# PCBArduino.net
KiCad netlist of a schematic drawn in EAGLE
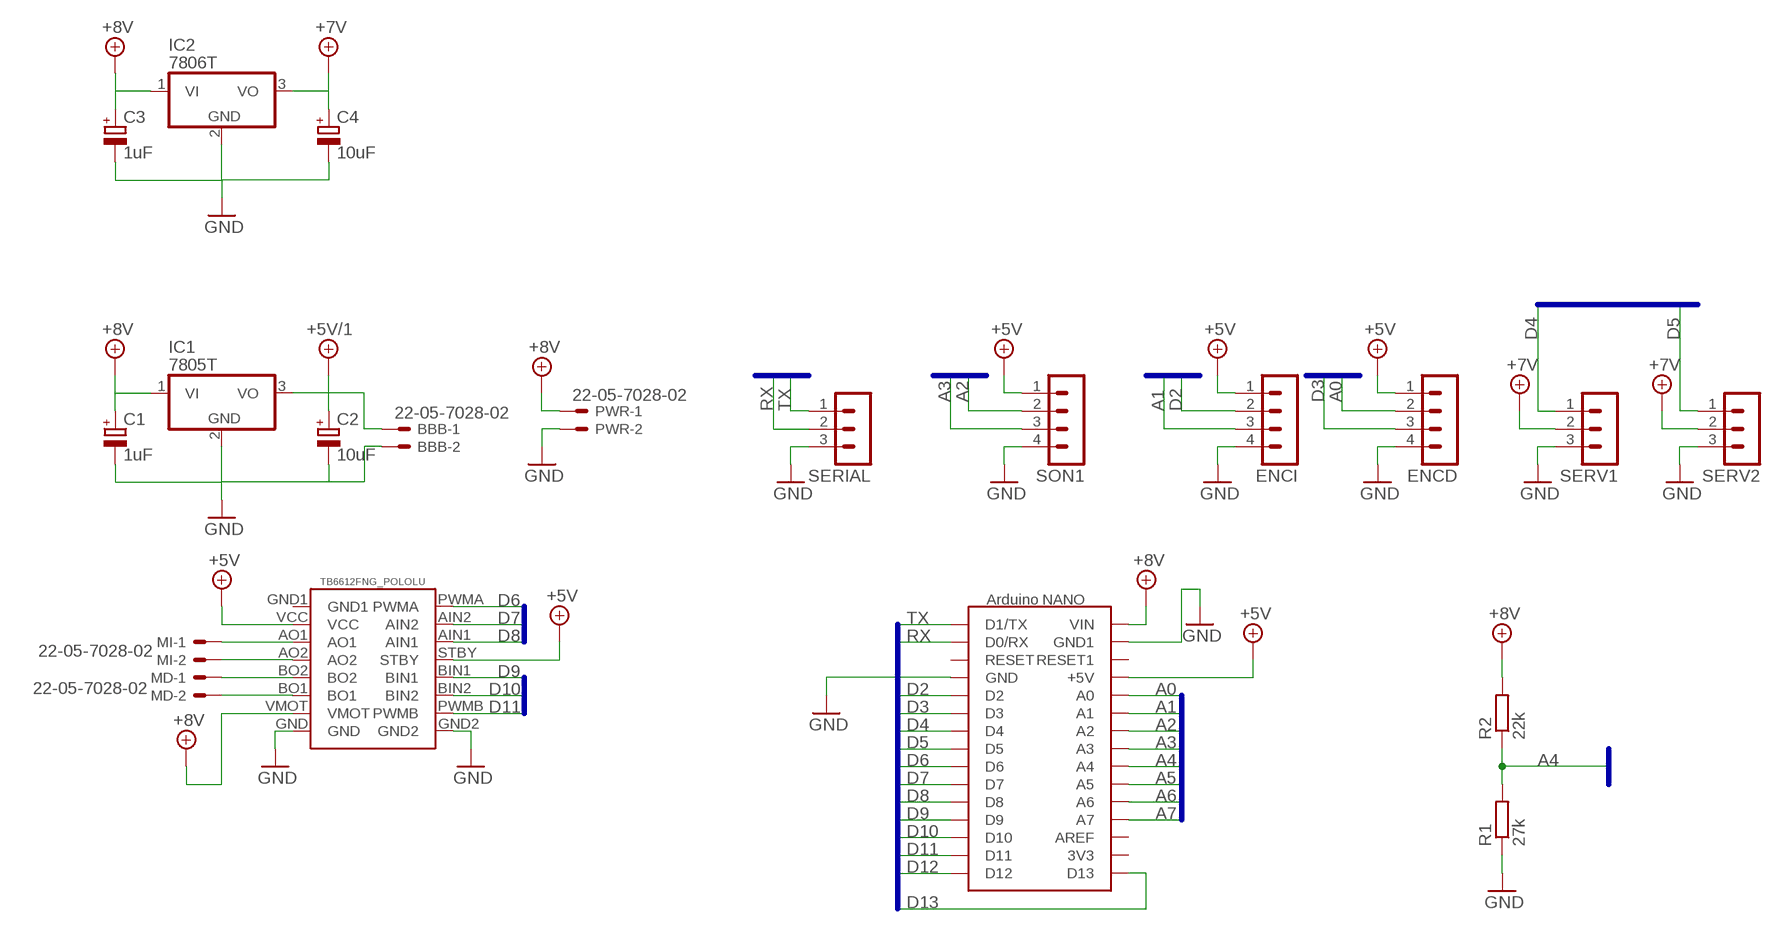
[diagram p0: schematic, sheet 1]

(export (version "E")
  (design (tool "Eeschema 10.0.6"))
  (components
    (comp (ref "BBB")
      (value "22-05-7028-02")
      (footprint "eagle-import:7395-02")
      (fields (field (name "OC_FARNELL") "9731601") (field (name "OC_NEWARK") "unknown"))
      (libsource (lib "eagle-import") (part "22-?-0205-7028"))
    )
    (comp (ref "C1")
      (value "1uF")
      (footprint "eagle-import:E2,5-7")
      (libsource (lib "eagle-import") (part "CPOL-EUE2.5-7"))
    )
    (comp (ref "C2")
      (value "10uF")
      (footprint "eagle-import:E2,5-7")
      (libsource (lib "eagle-import") (part "CPOL-EUE2.5-7"))
    )
    (comp (ref "C3")
      (value "1uF")
      (footprint "eagle-import:E2,5-7")
      (libsource (lib "eagle-import") (part "CPOL-EUE2.5-7"))
    )
    (comp (ref "C4")
      (value "10uF")
      (footprint "eagle-import:E2,5-7")
      (libsource (lib "eagle-import") (part "CPOL-EUE2.5-7"))
    )
    (comp (ref "ENCD")
      (value "MA04-1")
      (footprint "eagle-import:MA04-1")
      (libsource (lib "eagle-import") (part "MA04-1"))
    )
    (comp (ref "ENCI")
      (value "MA04-1")
      (footprint "eagle-import:MA04-1")
      (libsource (lib "eagle-import") (part "MA04-1"))
    )
    (comp (ref "IC1")
      (value "7805T")
      (footprint "eagle-import:TO220H")
      (libsource (lib "eagle-import") (part "78T05"))
    )
    (comp (ref "IC2")
      (value "7806T")
      (footprint "eagle-import:TO220H")
      (libsource (lib "eagle-import") (part "78T06"))
    )
    (comp (ref "MD")
      (value "22-05-7028-02")
      (footprint "eagle-import:7395-02")
      (libsource (lib "eagle-import") (part "22-?-0205-7028"))
    )
    (comp (ref "MI")
      (value "22-05-7028-02")
      (footprint "eagle-import:7395-02")
      (libsource (lib "eagle-import") (part "22-?-0205-7028"))
    )
    (comp (ref "PWR")
      (value "22-05-7028-02")
      (footprint "eagle-import:7395-02")
      (libsource (lib "eagle-import") (part "22-?-0205-7028"))
    )
    (comp (ref "R1")
      (value "27k")
      (footprint "eagle-import:0204_5")
      (libsource (lib "eagle-import") (part "R-EU_0204/5"))
    )
    (comp (ref "R2")
      (value "22k")
      (footprint "eagle-import:0204_5")
      (libsource (lib "eagle-import") (part "R-EU_0204/5"))
    )
    (comp (ref "SERIAL")
      (value "MA03-1")
      (footprint "eagle-import:MA03-1")
      (libsource (lib "eagle-import") (part "MA03-1"))
    )
    (comp (ref "SERV1")
      (value "MA03-1")
      (footprint "eagle-import:MA03-1")
      (libsource (lib "eagle-import") (part "MA03-1"))
    )
    (comp (ref "SERV2")
      (value "MA03-1")
      (footprint "eagle-import:MA03-1")
      (libsource (lib "eagle-import") (part "MA03-1"))
    )
    (comp (ref "SON1")
      (value "MA04-1")
      (footprint "eagle-import:MA04-1")
      (fields (field (name "OC_FARNELL") "unknown") (field (name "OC_NEWARK") "unknown"))
      (libsource (lib "eagle-import") (part "MA04-1"))
    )
    (comp (ref "U$1")
      (value "ARDUINONANO")
      (footprint "eagle-import:PDIP-32")
      (libsource (lib "eagle-import") (part "ARDUINONANO"))
    )
    (comp (ref "U$2")
      (value "TB6612FNG_POLOLU")
      (footprint "eagle-import:TB6612FNG_POLOLU")
      (libsource (lib "eagle-import") (part "TB6612FNG_POLOLU"))
    )
  )
  (nets
    (net (code "1") (name "+5V") (class "Default")
      (node (ref "ENCD") (pin "1") (pinfunction "1_1") (pintype "passive"))
      (node (ref "ENCI") (pin "1") (pinfunction "1_1") (pintype "passive"))
      (node (ref "SON1") (pin "1") (pinfunction "1_1") (pintype "passive"))
      (node (ref "U$1") (pin "+5V") (pinfunction "+5V_+5V") (pintype "bidirectional"))
      (node (ref "U$2") (pin "STBY") (pinfunction "STBY_STBY") (pintype "bidirectional"))
      (node (ref "U$2") (pin "VCC") (pinfunction "VCC_VCC") (pintype "bidirectional"))
    )
    (net (code "2") (name "+5V{slash}1") (class "Default")
      (node (ref "BBB") (pin "1") (pinfunction "S_1") (pintype "passive"))
      (node (ref "C2") (pin "+") (pinfunction "+_+") (pintype "passive"))
      (node (ref "IC1") (pin "3") (pinfunction "VO_3") (pintype "passive"))
    )
    (net (code "3") (name "+7V") (class "Default")
      (node (ref "C4") (pin "+") (pinfunction "+_+") (pintype "passive"))
      (node (ref "IC2") (pin "3") (pinfunction "VO_3") (pintype "passive"))
      (node (ref "SERV1") (pin "2") (pinfunction "2_2") (pintype "passive"))
      (node (ref "SERV2") (pin "2") (pinfunction "2_2") (pintype "passive"))
    )
    (net (code "4") (name "+8V") (class "Default")
      (node (ref "C1") (pin "+") (pinfunction "+_+") (pintype "passive"))
      (node (ref "C3") (pin "+") (pinfunction "+_+") (pintype "passive"))
      (node (ref "IC1") (pin "1") (pinfunction "VI_1") (pintype "input"))
      (node (ref "IC2") (pin "1") (pinfunction "VI_1") (pintype "input"))
      (node (ref "PWR") (pin "1") (pinfunction "S_1") (pintype "passive"))
      (node (ref "R2") (pin "2") (pinfunction "2_2") (pintype "passive"))
      (node (ref "U$1") (pin "VIN") (pinfunction "VIN_VIN") (pintype "bidirectional"))
      (node (ref "U$2") (pin "VMOT") (pinfunction "VMOT_VMOT") (pintype "bidirectional"))
    )
    (net (code "5") (name "/A0") (class "Default")
      (node (ref "ENCD") (pin "2") (pinfunction "2_2") (pintype "passive"))
      (node (ref "U$1") (pin "A0") (pinfunction "A0_A0") (pintype "bidirectional"))
    )
    (net (code "6") (name "/A1") (class "Default")
      (node (ref "ENCI") (pin "3") (pinfunction "3_3") (pintype "passive"))
      (node (ref "U$1") (pin "A1") (pinfunction "A1_A1") (pintype "bidirectional"))
    )
    (net (code "7") (name "/A2") (class "Default")
      (node (ref "SON1") (pin "2") (pinfunction "2_2") (pintype "passive"))
      (node (ref "U$1") (pin "A2") (pinfunction "A2_A2") (pintype "bidirectional"))
    )
    (net (code "8") (name "/A3") (class "Default")
      (node (ref "SON1") (pin "3") (pinfunction "3_3") (pintype "passive"))
      (node (ref "U$1") (pin "A3") (pinfunction "A3_A3") (pintype "bidirectional"))
    )
    (net (code "9") (name "/A4") (class "Default")
      (node (ref "R1") (pin "2") (pinfunction "2_2") (pintype "passive"))
      (node (ref "R2") (pin "1") (pinfunction "1_1") (pintype "passive"))
      (node (ref "U$1") (pin "A4") (pinfunction "A4_A4") (pintype "bidirectional"))
    )
    (net (code "10") (name "/A5") (class "Default")
      (node (ref "U$1") (pin "A5") (pinfunction "A5_A5") (pintype "bidirectional"))
    )
    (net (code "11") (name "/A6") (class "Default")
      (node (ref "U$1") (pin "A6") (pinfunction "A6_A6") (pintype "bidirectional"))
    )
    (net (code "12") (name "/A7") (class "Default")
      (node (ref "U$1") (pin "A7") (pinfunction "A7_A7") (pintype "bidirectional"))
    )
    (net (code "13") (name "/D2") (class "Default")
      (node (ref "ENCI") (pin "2") (pinfunction "2_2") (pintype "passive"))
      (node (ref "U$1") (pin "D2") (pinfunction "D2_D2") (pintype "bidirectional"))
    )
    (net (code "14") (name "/D3") (class "Default")
      (node (ref "ENCD") (pin "3") (pinfunction "3_3") (pintype "passive"))
      (node (ref "U$1") (pin "D3") (pinfunction "D3_D3") (pintype "bidirectional"))
    )
    (net (code "15") (name "/D4") (class "Default")
      (node (ref "SERV1") (pin "1") (pinfunction "1_1") (pintype "passive"))
      (node (ref "U$1") (pin "D4") (pinfunction "D4_D4") (pintype "bidirectional"))
    )
    (net (code "16") (name "/D5") (class "Default")
      (node (ref "SERV2") (pin "1") (pinfunction "1_1") (pintype "passive"))
      (node (ref "U$1") (pin "D5") (pinfunction "D5_D5") (pintype "bidirectional"))
    )
    (net (code "17") (name "/D6") (class "Default")
      (node (ref "U$1") (pin "D6") (pinfunction "D6_D6") (pintype "bidirectional"))
      (node (ref "U$2") (pin "PWMA") (pinfunction "PWMA_PWMA") (pintype "bidirectional"))
    )
    (net (code "18") (name "/D7") (class "Default")
      (node (ref "U$1") (pin "D7") (pinfunction "D7_D7") (pintype "bidirectional"))
      (node (ref "U$2") (pin "AIN2") (pinfunction "AIN2_AIN2") (pintype "bidirectional"))
    )
    (net (code "19") (name "/D8") (class "Default")
      (node (ref "U$1") (pin "D8") (pinfunction "D8_D8") (pintype "bidirectional"))
      (node (ref "U$2") (pin "AIN1") (pinfunction "AIN1_AIN1") (pintype "bidirectional"))
    )
    (net (code "20") (name "/D9") (class "Default")
      (node (ref "U$1") (pin "D9") (pinfunction "D9_D9") (pintype "bidirectional"))
      (node (ref "U$2") (pin "BIN1") (pinfunction "BIN1_BIN1") (pintype "bidirectional"))
    )
    (net (code "21") (name "/D10") (class "Default")
      (node (ref "U$1") (pin "D10") (pinfunction "D10_D10") (pintype "bidirectional"))
      (node (ref "U$2") (pin "BIN2") (pinfunction "BIN2_BIN2") (pintype "bidirectional"))
    )
    (net (code "22") (name "/D11") (class "Default")
      (node (ref "U$1") (pin "D11") (pinfunction "D11_D11") (pintype "bidirectional"))
      (node (ref "U$2") (pin "PWMB") (pinfunction "PWMB_PWMB") (pintype "bidirectional"))
    )
    (net (code "23") (name "/D12") (class "Default")
      (node (ref "U$1") (pin "D12") (pinfunction "D12_D12") (pintype "bidirectional"))
    )
    (net (code "24") (name "/D13") (class "Default")
      (node (ref "U$1") (pin "D13") (pinfunction "D13_D13") (pintype "bidirectional"))
    )
    (net (code "25") (name "/RX") (class "Default")
      (node (ref "SERIAL") (pin "2") (pinfunction "2_2") (pintype "passive"))
      (node (ref "U$1") (pin "D0/RX") (pinfunction "D0/RX_D0/RX") (pintype "bidirectional"))
    )
    (net (code "26") (name "/TX") (class "Default")
      (node (ref "SERIAL") (pin "1") (pinfunction "1_1") (pintype "passive"))
      (node (ref "U$1") (pin "D1/TX") (pinfunction "D1/TX_D1/TX") (pintype "bidirectional"))
    )
    (net (code "27") (name "GND") (class "Default")
      (node (ref "BBB") (pin "2") (pinfunction "S_2") (pintype "passive"))
      (node (ref "C1") (pin "-") (pinfunction "-_-") (pintype "passive"))
      (node (ref "C2") (pin "-") (pinfunction "-_-") (pintype "passive"))
      (node (ref "C3") (pin "-") (pinfunction "-_-") (pintype "passive"))
      (node (ref "C4") (pin "-") (pinfunction "-_-") (pintype "passive"))
      (node (ref "ENCD") (pin "4") (pinfunction "4_4") (pintype "passive"))
      (node (ref "ENCI") (pin "4") (pinfunction "4_4") (pintype "passive"))
      (node (ref "IC1") (pin "2") (pinfunction "GND_2") (pintype "passive"))
      (node (ref "IC2") (pin "2") (pinfunction "GND_2") (pintype "passive"))
      (node (ref "PWR") (pin "2") (pinfunction "S_2") (pintype "passive"))
      (node (ref "R1") (pin "1") (pinfunction "1_1") (pintype "passive"))
      (node (ref "SERIAL") (pin "3") (pinfunction "3_3") (pintype "passive"))
      (node (ref "SERV1") (pin "3") (pinfunction "3_3") (pintype "passive"))
      (node (ref "SERV2") (pin "3") (pinfunction "3_3") (pintype "passive"))
      (node (ref "SON1") (pin "4") (pinfunction "4_4") (pintype "passive"))
      (node (ref "U$1") (pin "GND") (pinfunction "GND_GND") (pintype "bidirectional"))
      (node (ref "U$1") (pin "GND1") (pinfunction "GND1_GND1") (pintype "bidirectional"))
      (node (ref "U$2") (pin "GND") (pinfunction "GND_GND") (pintype "bidirectional"))
      (node (ref "U$2") (pin "GND2") (pinfunction "GND2_GND2") (pintype "bidirectional"))
    )
    (net (code "28") (name "Net-(MDA-S)") (class "Default")
      (node (ref "MD") (pin "1") (pinfunction "S_1") (pintype "passive"))
      (node (ref "U$2") (pin "BO2") (pinfunction "BO2_BO2") (pintype "bidirectional"))
    )
    (net (code "29") (name "Net-(MDB-S)") (class "Default")
      (node (ref "MD") (pin "2") (pinfunction "S_2") (pintype "passive"))
      (node (ref "U$2") (pin "BO1") (pinfunction "BO1_BO1") (pintype "bidirectional"))
    )
    (net (code "30") (name "Net-(MIA-S)") (class "Default")
      (node (ref "MI") (pin "1") (pinfunction "S_1") (pintype "passive"))
      (node (ref "U$2") (pin "AO1") (pinfunction "AO1_AO1") (pintype "bidirectional"))
    )
    (net (code "31") (name "Net-(MIB-S)") (class "Default")
      (node (ref "MI") (pin "2") (pinfunction "S_2") (pintype "passive"))
      (node (ref "U$2") (pin "AO2") (pinfunction "AO2_AO2") (pintype "bidirectional"))
    )
    (net (code "32") (name "unconnected-(U$1-Pad3V3)") (class "Default")
      (node (ref "U$1") (pin "3V3") (pinfunction "3V3_3V3") (pintype "bidirectional"))
    )
    (net (code "33") (name "unconnected-(U$1-PadAREF)") (class "Default")
      (node (ref "U$1") (pin "AREF") (pinfunction "AREF_AREF") (pintype "bidirectional"))
    )
    (net (code "34") (name "unconnected-(U$1-PadRESET)") (class "Default")
      (node (ref "U$1") (pin "RESET") (pinfunction "RESET_RESET") (pintype "bidirectional"))
    )
    (net (code "35") (name "unconnected-(U$1-PadRESET1)") (class "Default")
      (node (ref "U$1") (pin "RESET1") (pinfunction "RESET1_RESET1") (pintype "bidirectional"))
    )
    (net (code "36") (name "unconnected-(U$2-PadGND1)") (class "Default")
      (node (ref "U$2") (pin "GND1") (pinfunction "GND1_GND1") (pintype "bidirectional"))
    )
  )
)
